# Sheet1.net
KiCad netlist of a schematic drawn in Altium Designer
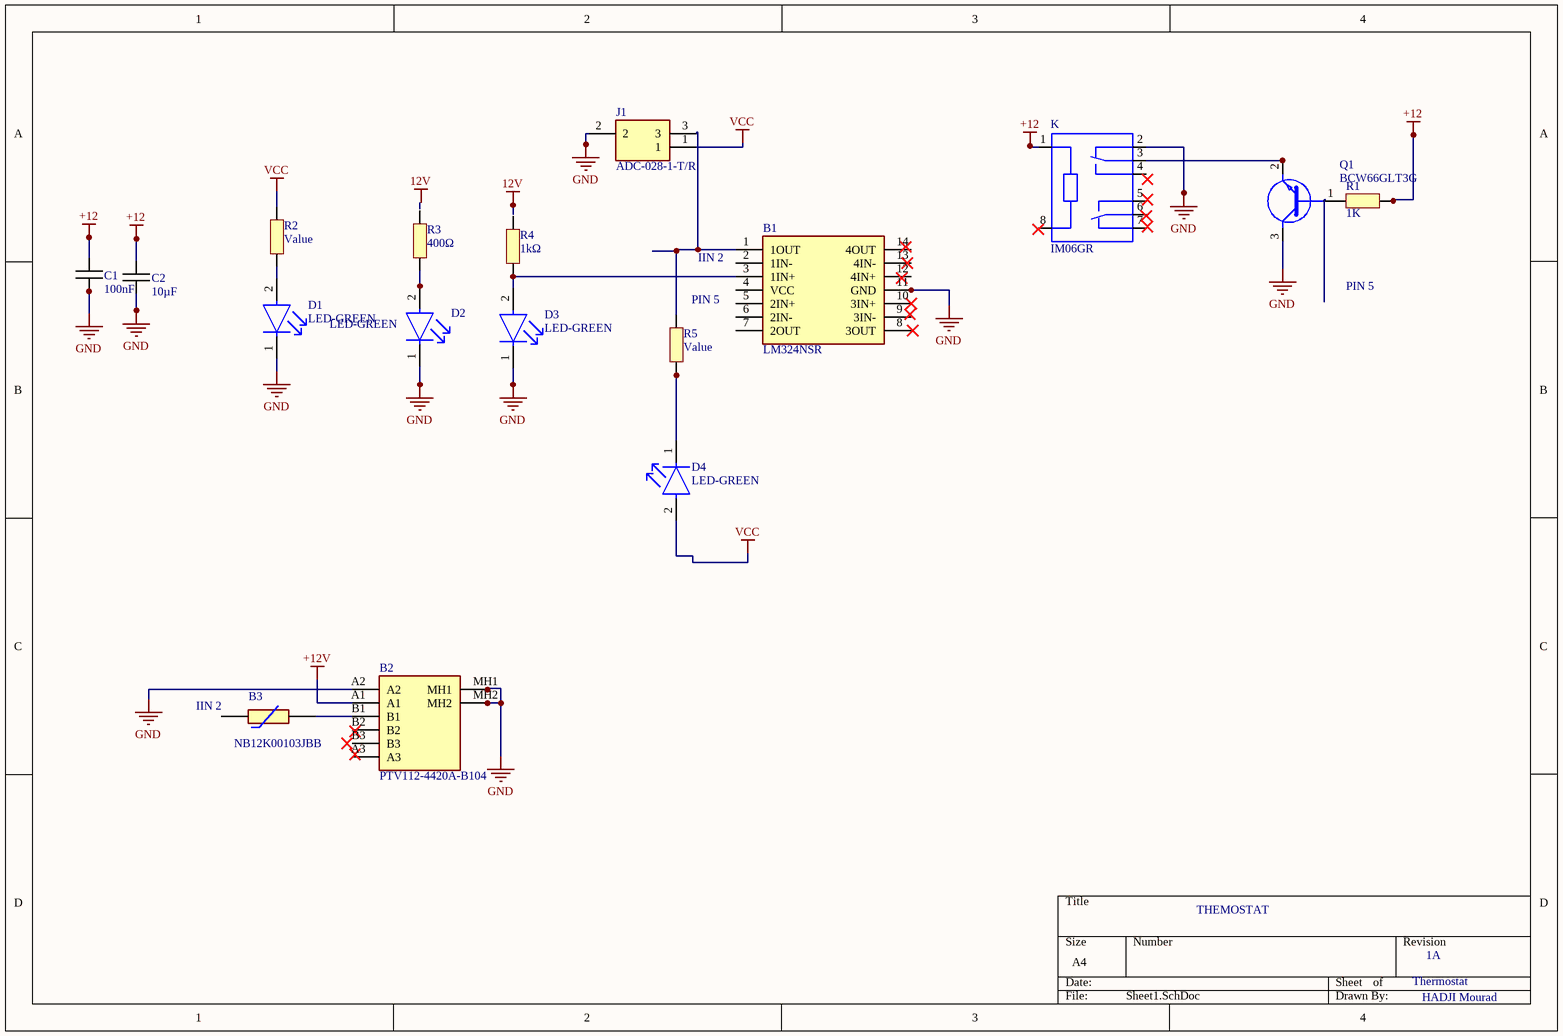
[diagram p0: Sheet1.SchDoc]

(export (version "E")
  (design (tool "Eeschema 10.0.6"))
  (components
    (comp (ref "B1")
      (value "LM324NSR")
      (footprint "SOIC127P780X200-14N")
      (description "Quadruple Operational Amplifier")
      (fields (field (name "MOUSER PART NUMBER") "595-LM324NSR"))
      (libsource (lib "Schlib1") (part "LM324NSR"))
    )
    (comp (ref "B2")
      (value "PTV112-4420A-B104")
      (footprint "PTV1124420AB104")
      (description "Potentiometers PANEL CONTROL 100kOhm")
      (fields (field (name "MOUSER PART NUMBER") "652-PTV1124420AB104"))
      (libsource (lib "Schlib1") (part "PTV112-4420A-B104"))
    )
    (comp (ref "B3")
      (value "NB12K00103JBB")
      (footprint "RESC2212X50N")
      (description "NTC SMD Thermistor, NB12K, 10K, 5% AVX 10k 0805 Protection NTC Thermistor, 5s, 2 x 1.25 x 1.3mm")
      (fields (field (name "MOUSER PART NUMBER") "581-NB12K00103JBB"))
      (libsource (lib "Schlib1") (part "NB12K00103JBB"))
    )
    (comp (ref "C1")
      (value "100nF")
      (footprint "CAPC1005X06N")
      (libsource (lib "Schlib1") (part "Capacitor"))
    )
    (comp (ref "C2") (value "10µF") (footprint "CAPC1005X06N") (libsource (lib "Schlib1") (part "Capacitor")))
    (comp (ref "D1")
      (value "LED-GREEN")
      (footprint "SMD-1608-LED")
      (description "LED GREEN CLEAR CHIP SMD LTST-C190GKT")
      (fields (field (name "VOLTAGE") "2V"))
      (libsource (lib "Schlib1") (part "LED-GREEN"))
    )
    (comp (ref "D2")
      (value "LED-GREEN")
      (footprint "SMD-1608-LED")
      (description "LED GREEN CLEAR CHIP SMD LTST-C190GKT")
      (fields (field (name "VOLTAGE") "2V"))
      (libsource (lib "Schlib1") (part "LED-GREEN"))
    )
    (comp (ref "D3")
      (value "LED-GREEN")
      (footprint "SMD-1608-LED")
      (description "LED GREEN CLEAR CHIP SMD LTST-C190GKT")
      (fields (field (name "VOLTAGE") "2V"))
      (libsource (lib "Schlib1") (part "LED-GREEN"))
    )
    (comp (ref "D4")
      (value "LED-GREEN")
      (footprint "SMD-1608-LED")
      (description "LED GREEN CLEAR CHIP SMD LTST-C190GKT")
      (fields (field (name "VOLTAGE") "2V"))
      (libsource (lib "Schlib1") (part "LED-GREEN"))
    )
    (comp (ref "J1")
      (value "ADC-028-1-T/R")
      (footprint "PJ1021SMTTR")
      (description "Connecteurs d'alimentation continue DC POWER JACK 2MM PIN TYPE 028")
      (fields (field (name "MOUSER PART NUMBER") "737-ADC-028-1-T/R"))
      (libsource (lib "Schlib1") (part "ADC-028-1-T/R"))
    )
    (comp (ref "K")
      (value "IM06GR")
      (footprint "RELAY_IM06GR")
      (description "Electromechanical Relay 12VDC 1.029KOhm 2A DPDT _10x7.5x5.65_mm SMD Signal Relay")
      (fields (field (name "MF") "TE Connectivity"))
      (libsource (lib "Schlib1") (part "IM06GR"))
    )
    (comp (ref "Q1")
      (value "BCW66GLT3G")
      (footprint "SOT96P237X111-3N")
      (description "NPN Bipolar Transistor")
      (fields (field (name "MOUSER PART NUMBER") "863-BCW66GLT3G"))
      (libsource (lib "Schlib1") (part "BCW66GLT3G"))
    )
    (comp (ref "R1") (value "1K") (footprint "RESC1005X06N") (libsource (lib "Schlib1") (part "Resistor")))
    (comp (ref "R2") (value "Value") (footprint "RESC1005X06N") (libsource (lib "") (part "Resistor_1")))
    (comp (ref "R3") (value "400Ω") (footprint "RESC1005X06N") (libsource (lib "") (part "Resistor_1")))
    (comp (ref "R4") (value "1kΩ") (footprint "RESC1005X06N") (libsource (lib "") (part "Resistor_1")))
    (comp (ref "R5") (value "Value") (footprint "RESC1005X06N") (libsource (lib "") (part "Resistor_1")))
  )
  (nets
    (net (code "1") (name "+12") (class "Default")
      (node (ref "C1") (pin "1") (pinfunction "1_1") (pintype "passive"))
      (node (ref "C2") (pin "1") (pinfunction "1_1") (pintype "passive"))
      (node (ref "K") (pin "1") (pinfunction "1_1") (pintype "passive"))
    )
    (net (code "2") (name "+12V") (class "Default")
      (node (ref "B2") (pin "A1") (pinfunction "A1_A1") (pintype "passive"))
    )
    (net (code "4") (name "GND") (class "Default")
      (node (ref "B1") (pin "11") (pinfunction "GND_11") (pintype "passive"))
      (node (ref "B2") (pin "A2") (pinfunction "A2_A2") (pintype "passive"))
      (node (ref "B2") (pin "MH1") (pinfunction "MH1_MH1") (pintype "passive"))
      (node (ref "B2") (pin "MH2") (pinfunction "MH2_MH2") (pintype "passive"))
      (node (ref "C1") (pin "2") (pinfunction "2_2") (pintype "passive"))
      (node (ref "C2") (pin "2") (pinfunction "2_2") (pintype "passive"))
      (node (ref "D1") (pin "1") (pinfunction "C_1") (pintype "passive"))
      (node (ref "D2") (pin "1") (pinfunction "C_1") (pintype "passive"))
      (node (ref "D3") (pin "1") (pinfunction "C_1") (pintype "passive"))
      (node (ref "J1") (pin "2") (pinfunction "2_2") (pintype "passive"))
      (node (ref "K") (pin "2") (pinfunction "2_2") (pintype "passive"))
      (node (ref "Q1") (pin "3") (pinfunction "C_3") (pintype "passive"))
    )
    (net (code "5") (name "Net-(B1-1OUT)") (class "Default")
      (node (ref "B1") (pin "1") (pinfunction "1OUT_1") (pintype "passive"))
      (node (ref "J1") (pin "3") (pinfunction "3_3") (pintype "passive"))
      (node (ref "R5") (pin "2") (pinfunction "2_2") (pintype "passive"))
    )
    (net (code "6") (name "Net-(B2-PadB1)") (class "Default")
      (node (ref "B2") (pin "B1") (pinfunction "B1_B1") (pintype "passive"))
      (node (ref "B3") (pin "2") (pinfunction "2_2") (pintype "passive"))
    )
    (net (code "7") (name "Net-(D1-A)") (class "Default")
      (node (ref "D1") (pin "2") (pinfunction "A_2") (pintype "passive"))
      (node (ref "R2") (pin "1") (pinfunction "1_1") (pintype "passive"))
    )
    (net (code "8") (name "Net-(D2-A)") (class "Default")
      (node (ref "D2") (pin "2") (pinfunction "A_2") (pintype "passive"))
      (node (ref "R3") (pin "1") (pinfunction "1_1") (pintype "passive"))
    )
    (net (code "9") (name "Net-(D3-A)") (class "Default")
      (node (ref "D3") (pin "2") (pinfunction "A_2") (pintype "passive"))
      (node (ref "R4") (pin "1") (pinfunction "1_1") (pintype "passive"))
    )
    (net (code "10") (name "Net-(D4-C)") (class "Default")
      (node (ref "D4") (pin "1") (pinfunction "C_1") (pintype "passive"))
      (node (ref "R5") (pin "1") (pinfunction "1_1") (pintype "passive"))
    )
    (net (code "11") (name "Net-(Q1-E)") (class "Default")
      (node (ref "K") (pin "3") (pinfunction "3_3") (pintype "passive"))
      (node (ref "Q1") (pin "2") (pinfunction "E_2") (pintype "passive"))
    )
    (net (code "12") (name "VCC") (class "Default")
      (node (ref "D4") (pin "2") (pinfunction "A_2") (pintype "passive"))
      (node (ref "J1") (pin "1") (pinfunction "1_1") (pintype "passive"))
      (node (ref "R2") (pin "2") (pinfunction "2_2") (pintype "passive"))
    )
    (net (code "13") (name "unconnected-(B1-1IN+-Pad3)") (class "Default")
      (node (ref "B1") (pin "3") (pinfunction "1IN+_3") (pintype "passive"))
    )
    (net (code "14") (name "unconnected-(B1-1IN--Pad2)") (class "Default")
      (node (ref "B1") (pin "2") (pinfunction "1IN-_2") (pintype "passive"))
    )
    (net (code "15") (name "unconnected-(B1-2IN+-Pad5)") (class "Default")
      (node (ref "B1") (pin "5") (pinfunction "2IN+_5") (pintype "passive"))
    )
    (net (code "16") (name "unconnected-(B1-2IN--Pad6)") (class "Default")
      (node (ref "B1") (pin "6") (pinfunction "2IN-_6") (pintype "passive"))
    )
    (net (code "17") (name "unconnected-(B1-2OUT-Pad7)") (class "Default")
      (node (ref "B1") (pin "7") (pinfunction "2OUT_7") (pintype "passive"))
    )
    (net (code "18") (name "unconnected-(B1-3IN+-Pad10)") (class "Default")
      (node (ref "B1") (pin "10") (pinfunction "3IN+_10") (pintype "passive+no_connect"))
    )
    (net (code "19") (name "unconnected-(B1-3IN--Pad9)") (class "Default")
      (node (ref "B1") (pin "9") (pinfunction "3IN-_9") (pintype "passive"))
    )
    (net (code "20") (name "unconnected-(B1-3OUT-Pad8)") (class "Default")
      (node (ref "B1") (pin "8") (pinfunction "3OUT_8") (pintype "passive"))
    )
    (net (code "21") (name "unconnected-(B1-4IN+-Pad12)") (class "Default")
      (node (ref "B1") (pin "12") (pinfunction "4IN+_12") (pintype "passive"))
    )
    (net (code "22") (name "unconnected-(B1-4IN--Pad13)") (class "Default")
      (node (ref "B1") (pin "13") (pinfunction "4IN-_13") (pintype "passive"))
    )
    (net (code "23") (name "unconnected-(B1-4OUT-Pad14)") (class "Default")
      (node (ref "B1") (pin "14") (pinfunction "4OUT_14") (pintype "passive"))
    )
    (net (code "24") (name "unconnected-(B1-VCC-Pad4)") (class "Default")
      (node (ref "B1") (pin "4") (pinfunction "VCC_4") (pintype "passive"))
    )
    (net (code "25") (name "unconnected-(B2-PadA3)") (class "Default")
      (node (ref "B2") (pin "A3") (pinfunction "A3_A3") (pintype "passive"))
    )
    (net (code "26") (name "unconnected-(B2-PadB2)") (class "Default")
      (node (ref "B2") (pin "B2") (pinfunction "B2_B2") (pintype "passive"))
    )
    (net (code "27") (name "unconnected-(B2-PadB3)") (class "Default")
      (node (ref "B2") (pin "B3") (pinfunction "B3_B3") (pintype "passive"))
    )
    (net (code "28") (name "unconnected-(B3-Pad1)") (class "Default")
      (node (ref "B3") (pin "1") (pinfunction "1_1") (pintype "passive"))
    )
    (net (code "29") (name "unconnected-(K-Pad4)") (class "Default")
      (node (ref "K") (pin "4") (pinfunction "4_4") (pintype "passive"))
    )
    (net (code "30") (name "unconnected-(K-Pad5)") (class "Default")
      (node (ref "K") (pin "5") (pinfunction "5_5") (pintype "passive"))
    )
    (net (code "31") (name "unconnected-(K-Pad6)") (class "Default")
      (node (ref "K") (pin "6") (pinfunction "6_6") (pintype "passive"))
    )
    (net (code "32") (name "unconnected-(K-Pad7)") (class "Default")
      (node (ref "K") (pin "7") (pinfunction "7_7") (pintype "passive"))
    )
    (net (code "33") (name "unconnected-(K-Pad8)") (class "Default")
      (node (ref "K") (pin "8") (pinfunction "8_8") (pintype "passive"))
    )
    (net (code "34") (name "unconnected-(Q1-B-Pad1)") (class "Default")
      (node (ref "Q1") (pin "1") (pinfunction "B_1") (pintype "passive"))
    )
    (net (code "35") (name "unconnected-(R1-Pad1)") (class "Default")
      (node (ref "R1") (pin "1") (pinfunction "1_1") (pintype "passive"))
    )
    (net (code "36") (name "unconnected-(R1-Pad2)") (class "Default")
      (node (ref "R1") (pin "2") (pinfunction "2_2") (pintype "passive"))
    )
    (net (code "37") (name "unconnected-(R3-Pad2)") (class "Default")
      (node (ref "R3") (pin "2") (pinfunction "2_2") (pintype "passive"))
    )
    (net (code "38") (name "unconnected-(R4-Pad2)") (class "Default")
      (node (ref "R4") (pin "2") (pinfunction "2_2") (pintype "passive"))
    )
  )
)
